# Tape_Sensor_Circuit.net
KiCad netlist of a schematic drawn in EAGLE
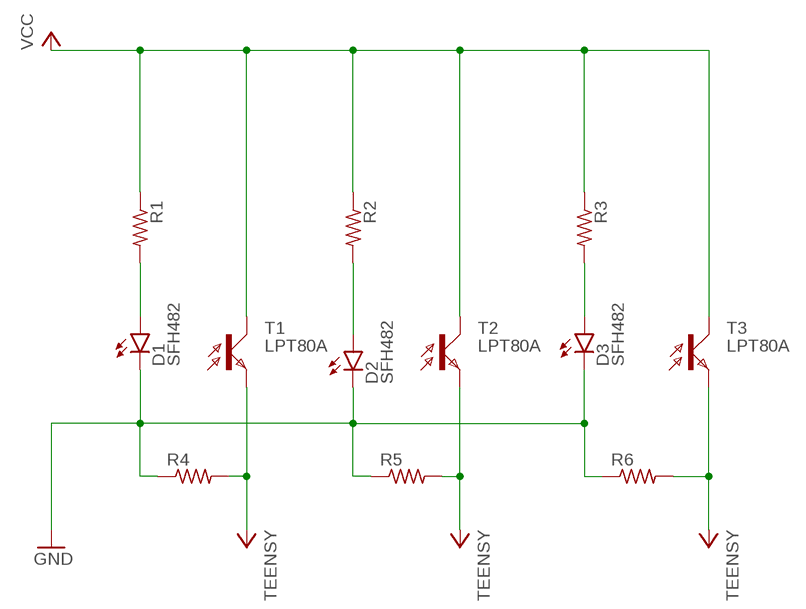
[diagram p0: schematic, sheet 1]

(export (version "E")
  (design (tool "Eeschema 10.0.6"))
  (components
    (comp (ref "D1")
      (value "SFH482")
      (footprint "eagle-import:SFH482")
      (libsource (lib "eagle-import") (part "SFH482"))
    )
    (comp (ref "D2")
      (value "SFH482")
      (footprint "eagle-import:SFH482")
      (libsource (lib "eagle-import") (part "SFH482"))
    )
    (comp (ref "D3")
      (value "SFH482")
      (footprint "eagle-import:SFH482")
      (libsource (lib "eagle-import") (part "SFH482"))
    )
    (comp (ref "R1")
      (value "R-US_0204/2V")
      (footprint "eagle-import:0204V")
      (libsource (lib "eagle-import") (part "R-US_0204/2V"))
    )
    (comp (ref "R2")
      (value "R-US_0204/2V")
      (footprint "eagle-import:0204V")
      (libsource (lib "eagle-import") (part "R-US_0204/2V"))
    )
    (comp (ref "R3")
      (value "R-US_0204/2V")
      (footprint "eagle-import:0204V")
      (libsource (lib "eagle-import") (part "R-US_0204/2V"))
    )
    (comp (ref "R4")
      (value "R-US_0204/2V")
      (footprint "eagle-import:0204V")
      (libsource (lib "eagle-import") (part "R-US_0204/2V"))
    )
    (comp (ref "R5")
      (value "R-US_0204/2V")
      (footprint "eagle-import:0204V")
      (libsource (lib "eagle-import") (part "R-US_0204/2V"))
    )
    (comp (ref "R6")
      (value "R-US_0204/2V")
      (footprint "eagle-import:0204V")
      (libsource (lib "eagle-import") (part "R-US_0204/2V"))
    )
    (comp (ref "T1")
      (value "LPT80A")
      (footprint "eagle-import:LPT80A")
      (libsource (lib "eagle-import") (part "LPT80A"))
    )
    (comp (ref "T2")
      (value "LPT80A")
      (footprint "eagle-import:LPT80A")
      (libsource (lib "eagle-import") (part "LPT80A"))
    )
    (comp (ref "T3")
      (value "LPT80A")
      (footprint "eagle-import:LPT80A")
      (libsource (lib "eagle-import") (part "LPT80A"))
    )
  )
  (nets
    (net (code "1") (name "GND") (class "Default")
      (node (ref "D1") (pin "K") (pinfunction "C_K") (pintype "passive"))
      (node (ref "D2") (pin "K") (pinfunction "C_K") (pintype "passive"))
      (node (ref "D3") (pin "K") (pinfunction "C_K") (pintype "passive"))
      (node (ref "R4") (pin "1") (pinfunction "1_1") (pintype "passive"))
      (node (ref "R5") (pin "1") (pinfunction "1_1") (pintype "passive"))
      (node (ref "R6") (pin "1") (pinfunction "1_1") (pintype "passive"))
    )
    (net (code "2") (name "Net-(D1-PadA)") (class "Default")
      (node (ref "D1") (pin "A") (pinfunction "A_A") (pintype "passive"))
      (node (ref "R1") (pin "2") (pinfunction "2_2") (pintype "passive"))
    )
    (net (code "3") (name "Net-(D2-PadA)") (class "Default")
      (node (ref "D2") (pin "A") (pinfunction "A_A") (pintype "passive"))
      (node (ref "R2") (pin "2") (pinfunction "2_2") (pintype "passive"))
    )
    (net (code "4") (name "Net-(D3-PadA)") (class "Default")
      (node (ref "D3") (pin "A") (pinfunction "A_A") (pintype "passive"))
      (node (ref "R3") (pin "2") (pinfunction "2_2") (pintype "passive"))
    )
    (net (code "5") (name "TEENSY") (class "Default")
      (node (ref "R1") (pin "1") (pinfunction "1_1") (pintype "passive"))
      (node (ref "R2") (pin "1") (pinfunction "1_1") (pintype "passive"))
      (node (ref "R3") (pin "1") (pinfunction "1_1") (pintype "passive"))
      (node (ref "R4") (pin "2") (pinfunction "2_2") (pintype "passive"))
      (node (ref "R5") (pin "2") (pinfunction "2_2") (pintype "passive"))
      (node (ref "R6") (pin "2") (pinfunction "2_2") (pintype "passive"))
      (node (ref "T1") (pin "C") (pinfunction "C_C") (pintype "passive"))
      (node (ref "T1") (pin "E") (pinfunction "E_E") (pintype "passive"))
      (node (ref "T2") (pin "C") (pinfunction "C_C") (pintype "passive"))
      (node (ref "T2") (pin "E") (pinfunction "E_E") (pintype "passive"))
      (node (ref "T3") (pin "C") (pinfunction "C_C") (pintype "passive"))
      (node (ref "T3") (pin "E") (pinfunction "E_E") (pintype "passive"))
    )
  )
)
